# CajitaAbierta_v07_robotique.net
KiCad netlist of a schematic drawn in EAGLE
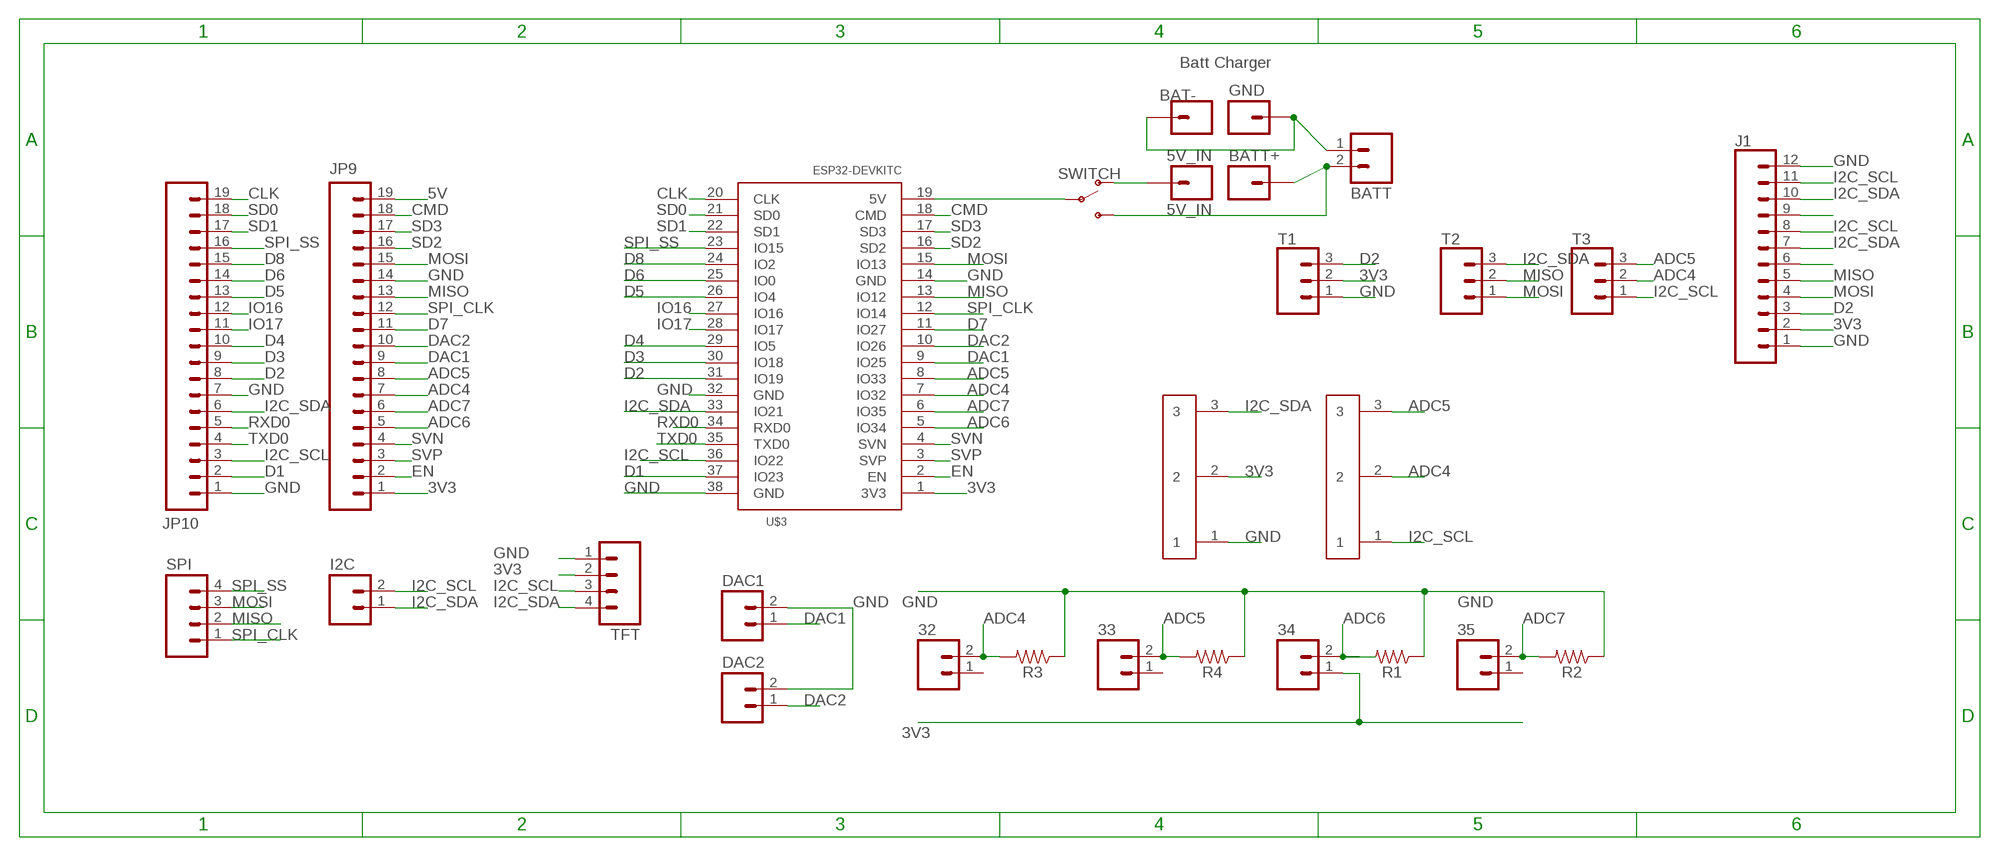
[diagram p0: schematic, sheet 1]

(export (version "E")
  (design (tool "Eeschema 10.0.6"))
  (components
    (comp (ref "5V_IN")
      (value "5V_IN")
      (footprint "eagle-import:1X01")
      (libsource (lib "eagle-import") (part "M01PTH"))
    )
    (comp (ref "32")
      (value "M02PTH")
      (footprint "eagle-import:1X02")
      (libsource (lib "eagle-import") (part "SparkFun-Connectors_6242394_M02PTH"))
    )
    (comp (ref "33")
      (value "M02PTH")
      (footprint "eagle-import:1X02")
      (libsource (lib "eagle-import") (part "SparkFun-Connectors_6242394_M02PTH"))
    )
    (comp (ref "34")
      (value "M02PTH")
      (footprint "eagle-import:1X02")
      (libsource (lib "eagle-import") (part "SparkFun-Connectors_6242394_M02PTH"))
    )
    (comp (ref "35")
      (value "M02PTH")
      (footprint "eagle-import:1X02")
      (libsource (lib "eagle-import") (part "SparkFun-Connectors_6242394_M02PTH"))
    )
    (comp (ref "BAT-")
      (value "M01PTH")
      (footprint "eagle-import:1X01")
      (libsource (lib "eagle-import") (part "M01PTH"))
    )
    (comp (ref "BATT")
      (value "M02LOCK_LONGPADS")
      (footprint "eagle-import:1X02_LOCK_LONGPADS")
      (libsource (lib "eagle-import") (part "M02LOCK_LONGPADS"))
    )
    (comp (ref "BATT+")
      (value "M01PTH")
      (footprint "eagle-import:1X01")
      (libsource (lib "eagle-import") (part "M01PTH"))
    )
    (comp (ref "DAC1")
      (value "M02PTH")
      (footprint "eagle-import:1X02")
      (libsource (lib "eagle-import") (part "SparkFun-Connectors_6242394_M02PTH"))
    )
    (comp (ref "DAC2")
      (value "M02PTH")
      (footprint "eagle-import:1X02")
      (libsource (lib "eagle-import") (part "SparkFun-Connectors_6242394_M02PTH"))
    )
    (comp (ref "GND")
      (value "Batt Charger")
      (footprint "eagle-import:1X01")
      (libsource (lib "eagle-import") (part "M01PTH"))
    )
    (comp (ref "I2C")
      (value "M02PTH")
      (footprint "eagle-import:1X02")
      (libsource (lib "eagle-import") (part "SparkFun-Connectors_6242394_M02PTH"))
    )
    (comp (ref "J1")
      (value "CONN_12NO_SILK")
      (footprint "eagle-import:1X12_NO_SILK")
      (libsource (lib "eagle-import") (part "CONN_12NO_SILK"))
    )
    (comp (ref "JP9")
      (value "M191X19")
      (footprint "eagle-import:1X19")
      (libsource (lib "eagle-import") (part "M191X19"))
    )
    (comp (ref "JP10")
      (value "M191X19")
      (footprint "eagle-import:1X19")
      (libsource (lib "eagle-import") (part "M191X19"))
    )
    (comp (ref "R1")
      (value "RESISTOR1206")
      (footprint "eagle-import:1206")
      (libsource (lib "eagle-import") (part "RESISTOR1206"))
    )
    (comp (ref "R2")
      (value "RESISTOR1206")
      (footprint "eagle-import:1206")
      (libsource (lib "eagle-import") (part "RESISTOR1206"))
    )
    (comp (ref "R3")
      (value "RESISTOR1206")
      (footprint "eagle-import:1206")
      (libsource (lib "eagle-import") (part "RESISTOR1206"))
    )
    (comp (ref "R4")
      (value "RESISTOR1206")
      (footprint "eagle-import:1206")
      (libsource (lib "eagle-import") (part "RESISTOR1206"))
    )
    (comp (ref "SPI")
      (value "M04PTH")
      (footprint "eagle-import:1X04")
      (libsource (lib "eagle-import") (part "M04PTH"))
    )
    (comp (ref "SWITCH")
      (value "SWITCH-SPDT-SMD-RIGHT-ANGLE")
      (footprint "eagle-import:SWITCH_SPST_SMD_A")
      (libsource (lib "eagle-import") (part "SWITCH-SPDT-SMD-RIGHT-ANGLE"))
    )
    (comp (ref "T1")
      (value "CONN_03SCREW-NS")
      (footprint "eagle-import:SCREWTERMINAL-3.5MM-3-NS")
      (libsource (lib "eagle-import") (part "CONN_03SCREW-NS"))
    )
    (comp (ref "T2")
      (value "CONN_03SCREW-NS")
      (footprint "eagle-import:SCREWTERMINAL-3.5MM-3-NS")
      (libsource (lib "eagle-import") (part "CONN_03SCREW-NS"))
    )
    (comp (ref "T3")
      (value "CONN_03SCREW-NS")
      (footprint "eagle-import:SCREWTERMINAL-3.5MM-3-NS")
      (libsource (lib "eagle-import") (part "CONN_03SCREW-NS"))
    )
    (comp (ref "TFT")
      (value "M04PTH")
      (footprint "eagle-import:1X04")
      (libsource (lib "eagle-import") (part "M04PTH"))
    )
    (comp (ref "U$3")
      (value "ESP32DEVKITC")
      (footprint "eagle-import:ESP32-DEVKITC")
      (libsource (lib "eagle-import") (part "ESP32DEVKITC"))
    )
    (comp (ref "U$4")
      (value "SCREW_TERMINAL_3_POS_5MM")
      (footprint "eagle-import:SCREW_TERMINAL_3_POS_5MM")
      (libsource (lib "eagle-import") (part "SCREW_TERMINAL_3_POS_5MM"))
    )
    (comp (ref "U$5")
      (value "SCREW_TERMINAL_3_POS_5MM")
      (footprint "eagle-import:SCREW_TERMINAL_3_POS_5MM")
      (libsource (lib "eagle-import") (part "SCREW_TERMINAL_3_POS_5MM"))
    )
  )
  (nets
    (net (code "1") (name "/3V3") (class "Default")
      (node (ref "34") (pin "1") (pinfunction "1_1") (pintype "passive"))
      (node (ref "J1") (pin "2") (pinfunction "2_2") (pintype "passive"))
      (node (ref "JP9") (pin "1") (pinfunction "1_1") (pintype "passive"))
      (node (ref "T1") (pin "2") (pinfunction "2_2") (pintype "passive"))
      (node (ref "TFT") (pin "2") (pinfunction "2_2") (pintype "passive"))
      (node (ref "U$3") (pin "1") (pinfunction "3V3_1") (pintype "bidirectional"))
      (node (ref "U$4") (pin "2") (pinfunction "2_2") (pintype "bidirectional"))
    )
    (net (code "2") (name "/5V") (class "Default")
      (node (ref "JP9") (pin "19") (pinfunction "19_19") (pintype "passive"))
      (node (ref "SWITCH") (pin "2") (pinfunction "P_2") (pintype "passive"))
      (node (ref "U$3") (pin "19") (pinfunction "5V_19") (pintype "bidirectional"))
    )
    (net (code "3") (name "/ADC4") (class "Default")
      (node (ref "32") (pin "2") (pinfunction "2_2") (pintype "passive"))
      (node (ref "JP9") (pin "7") (pinfunction "7_7") (pintype "passive"))
      (node (ref "R3") (pin "2") (pinfunction "2_2") (pintype "passive"))
      (node (ref "T3") (pin "2") (pinfunction "2_2") (pintype "passive"))
      (node (ref "U$3") (pin "7") (pinfunction "IO32_7") (pintype "bidirectional"))
      (node (ref "U$5") (pin "2") (pinfunction "2_2") (pintype "bidirectional"))
    )
    (net (code "4") (name "/ADC5") (class "Default")
      (node (ref "33") (pin "2") (pinfunction "2_2") (pintype "passive"))
      (node (ref "JP9") (pin "8") (pinfunction "8_8") (pintype "passive"))
      (node (ref "R4") (pin "2") (pinfunction "2_2") (pintype "passive"))
      (node (ref "T3") (pin "3") (pinfunction "3_3") (pintype "passive"))
      (node (ref "U$3") (pin "8") (pinfunction "IO33_8") (pintype "bidirectional"))
      (node (ref "U$5") (pin "3") (pinfunction "3_3") (pintype "bidirectional"))
    )
    (net (code "5") (name "/ADC6") (class "Default")
      (node (ref "34") (pin "2") (pinfunction "2_2") (pintype "passive"))
      (node (ref "JP9") (pin "5") (pinfunction "5_5") (pintype "passive"))
      (node (ref "R1") (pin "2") (pinfunction "2_2") (pintype "passive"))
      (node (ref "U$3") (pin "5") (pinfunction "IO34_5") (pintype "bidirectional"))
    )
    (net (code "6") (name "/ADC7") (class "Default")
      (node (ref "35") (pin "2") (pinfunction "2_2") (pintype "passive"))
      (node (ref "JP9") (pin "6") (pinfunction "6_6") (pintype "passive"))
      (node (ref "R2") (pin "2") (pinfunction "2_2") (pintype "passive"))
      (node (ref "U$3") (pin "6") (pinfunction "IO35_6") (pintype "bidirectional"))
    )
    (net (code "7") (name "/CLK") (class "Default")
      (node (ref "JP10") (pin "19") (pinfunction "19_19") (pintype "passive"))
      (node (ref "U$3") (pin "20") (pinfunction "CLK_20") (pintype "bidirectional"))
    )
    (net (code "8") (name "/CMD") (class "Default")
      (node (ref "JP9") (pin "18") (pinfunction "18_18") (pintype "passive"))
      (node (ref "U$3") (pin "18") (pinfunction "CMD_18") (pintype "bidirectional"))
    )
    (net (code "9") (name "/D1") (class "Default")
      (node (ref "JP10") (pin "2") (pinfunction "2_2") (pintype "passive"))
      (node (ref "U$3") (pin "37") (pinfunction "IO23_37") (pintype "bidirectional"))
    )
    (net (code "10") (name "/D2") (class "Default")
      (node (ref "J1") (pin "3") (pinfunction "3_3") (pintype "passive"))
      (node (ref "JP10") (pin "8") (pinfunction "8_8") (pintype "passive"))
      (node (ref "T1") (pin "3") (pinfunction "3_3") (pintype "passive"))
      (node (ref "U$3") (pin "31") (pinfunction "IO19_31") (pintype "bidirectional"))
    )
    (net (code "11") (name "/D3") (class "Default")
      (node (ref "JP10") (pin "9") (pinfunction "9_9") (pintype "passive"))
      (node (ref "U$3") (pin "30") (pinfunction "IO18_30") (pintype "bidirectional"))
    )
    (net (code "12") (name "/D4") (class "Default")
      (node (ref "JP10") (pin "10") (pinfunction "10_10") (pintype "passive"))
      (node (ref "U$3") (pin "29") (pinfunction "IO5_29") (pintype "bidirectional"))
    )
    (net (code "13") (name "/D5") (class "Default")
      (node (ref "JP10") (pin "13") (pinfunction "13_13") (pintype "passive"))
      (node (ref "U$3") (pin "26") (pinfunction "IO4_26") (pintype "bidirectional"))
    )
    (net (code "14") (name "/D6") (class "Default")
      (node (ref "JP10") (pin "14") (pinfunction "14_14") (pintype "passive"))
      (node (ref "U$3") (pin "25") (pinfunction "IO0_25") (pintype "bidirectional"))
    )
    (net (code "15") (name "/D7") (class "Default")
      (node (ref "JP9") (pin "11") (pinfunction "11_11") (pintype "passive"))
      (node (ref "U$3") (pin "11") (pinfunction "IO27_11") (pintype "bidirectional"))
    )
    (net (code "16") (name "/D8") (class "Default")
      (node (ref "JP10") (pin "15") (pinfunction "15_15") (pintype "passive"))
      (node (ref "U$3") (pin "24") (pinfunction "IO2_24") (pintype "bidirectional"))
    )
    (net (code "17") (name "/DAC1") (class "Default")
      (node (ref "DAC1") (pin "1") (pinfunction "1_1") (pintype "passive"))
      (node (ref "JP9") (pin "9") (pinfunction "9_9") (pintype "passive"))
      (node (ref "U$3") (pin "9") (pinfunction "IO25_9") (pintype "bidirectional"))
    )
    (net (code "18") (name "/DAC2") (class "Default")
      (node (ref "DAC2") (pin "1") (pinfunction "1_1") (pintype "passive"))
      (node (ref "JP9") (pin "10") (pinfunction "10_10") (pintype "passive"))
      (node (ref "U$3") (pin "10") (pinfunction "IO26_10") (pintype "bidirectional"))
    )
    (net (code "19") (name "/EN") (class "Default")
      (node (ref "JP9") (pin "2") (pinfunction "2_2") (pintype "passive"))
      (node (ref "U$3") (pin "2") (pinfunction "EN_2") (pintype "bidirectional"))
    )
    (net (code "20") (name "/GND") (class "Default")
      (node (ref "BAT-") (pin "1") (pinfunction "1_1") (pintype "passive"))
      (node (ref "BATT") (pin "1") (pinfunction "1_1") (pintype "passive"))
      (node (ref "DAC1") (pin "2") (pinfunction "2_2") (pintype "passive"))
      (node (ref "DAC2") (pin "2") (pinfunction "2_2") (pintype "passive"))
      (node (ref "GND") (pin "1") (pinfunction "1_1") (pintype "passive"))
      (node (ref "J1") (pin "1") (pinfunction "1_1") (pintype "passive"))
      (node (ref "J1") (pin "12") (pinfunction "12_12") (pintype "passive"))
      (node (ref "JP10") (pin "1") (pinfunction "1_1") (pintype "passive"))
      (node (ref "JP10") (pin "7") (pinfunction "7_7") (pintype "passive"))
      (node (ref "JP9") (pin "14") (pinfunction "14_14") (pintype "passive"))
      (node (ref "R1") (pin "1") (pinfunction "1_1") (pintype "passive"))
      (node (ref "R2") (pin "1") (pinfunction "1_1") (pintype "passive"))
      (node (ref "R3") (pin "1") (pinfunction "1_1") (pintype "passive"))
      (node (ref "R4") (pin "1") (pinfunction "1_1") (pintype "passive"))
      (node (ref "T1") (pin "1") (pinfunction "1_1") (pintype "passive"))
      (node (ref "TFT") (pin "1") (pinfunction "1_1") (pintype "passive"))
      (node (ref "U$3") (pin "14") (pinfunction "GND_14") (pintype "bidirectional"))
      (node (ref "U$3") (pin "32") (pinfunction "GND_32") (pintype "bidirectional"))
      (node (ref "U$3") (pin "38") (pinfunction "GND_38") (pintype "bidirectional"))
      (node (ref "U$4") (pin "1") (pinfunction "1_1") (pintype "bidirectional"))
    )
    (net (code "21") (name "/I2C_SCL") (class "Default")
      (node (ref "I2C") (pin "2") (pinfunction "2_2") (pintype "passive"))
      (node (ref "J1") (pin "11") (pinfunction "11_11") (pintype "passive"))
      (node (ref "J1") (pin "8") (pinfunction "8_8") (pintype "passive"))
      (node (ref "JP10") (pin "3") (pinfunction "3_3") (pintype "passive"))
      (node (ref "T3") (pin "1") (pinfunction "1_1") (pintype "passive"))
      (node (ref "TFT") (pin "3") (pinfunction "3_3") (pintype "passive"))
      (node (ref "U$3") (pin "36") (pinfunction "IO22_36") (pintype "bidirectional"))
      (node (ref "U$5") (pin "1") (pinfunction "1_1") (pintype "bidirectional"))
    )
    (net (code "22") (name "/I2C_SDA") (class "Default")
      (node (ref "I2C") (pin "1") (pinfunction "1_1") (pintype "passive"))
      (node (ref "J1") (pin "10") (pinfunction "10_10") (pintype "passive"))
      (node (ref "J1") (pin "7") (pinfunction "7_7") (pintype "passive"))
      (node (ref "JP10") (pin "6") (pinfunction "6_6") (pintype "passive"))
      (node (ref "T2") (pin "3") (pinfunction "3_3") (pintype "passive"))
      (node (ref "TFT") (pin "4") (pinfunction "4_4") (pintype "passive"))
      (node (ref "U$3") (pin "33") (pinfunction "IO21_33") (pintype "bidirectional"))
      (node (ref "U$4") (pin "3") (pinfunction "3_3") (pintype "bidirectional"))
    )
    (net (code "23") (name "/IO16") (class "Default")
      (node (ref "JP10") (pin "12") (pinfunction "12_12") (pintype "passive"))
      (node (ref "U$3") (pin "27") (pinfunction "IO16_27") (pintype "bidirectional"))
    )
    (net (code "24") (name "/IO17") (class "Default")
      (node (ref "JP10") (pin "11") (pinfunction "11_11") (pintype "passive"))
      (node (ref "U$3") (pin "28") (pinfunction "IO17_28") (pintype "bidirectional"))
    )
    (net (code "25") (name "/MISO") (class "Default")
      (node (ref "J1") (pin "5") (pinfunction "5_5") (pintype "passive"))
      (node (ref "JP9") (pin "13") (pinfunction "13_13") (pintype "passive"))
      (node (ref "SPI") (pin "2") (pinfunction "2_2") (pintype "passive"))
      (node (ref "T2") (pin "2") (pinfunction "2_2") (pintype "passive"))
      (node (ref "U$3") (pin "13") (pinfunction "IO12_13") (pintype "bidirectional"))
    )
    (net (code "26") (name "/MOSI") (class "Default")
      (node (ref "J1") (pin "4") (pinfunction "4_4") (pintype "passive"))
      (node (ref "JP9") (pin "15") (pinfunction "15_15") (pintype "passive"))
      (node (ref "SPI") (pin "3") (pinfunction "3_3") (pintype "passive"))
      (node (ref "T2") (pin "1") (pinfunction "1_1") (pintype "passive"))
      (node (ref "U$3") (pin "15") (pinfunction "IO13_15") (pintype "bidirectional"))
    )
    (net (code "27") (name "/RXD0") (class "Default")
      (node (ref "JP10") (pin "5") (pinfunction "5_5") (pintype "passive"))
      (node (ref "U$3") (pin "34") (pinfunction "RXD0_34") (pintype "bidirectional"))
    )
    (net (code "28") (name "/SD0") (class "Default")
      (node (ref "JP10") (pin "18") (pinfunction "18_18") (pintype "passive"))
      (node (ref "U$3") (pin "21") (pinfunction "SD0_21") (pintype "bidirectional"))
    )
    (net (code "29") (name "/SD1") (class "Default")
      (node (ref "JP10") (pin "17") (pinfunction "17_17") (pintype "passive"))
      (node (ref "U$3") (pin "22") (pinfunction "SD1_22") (pintype "bidirectional"))
    )
    (net (code "30") (name "/SD2") (class "Default")
      (node (ref "JP9") (pin "16") (pinfunction "16_16") (pintype "passive"))
      (node (ref "U$3") (pin "16") (pinfunction "SD2_16") (pintype "bidirectional"))
    )
    (net (code "31") (name "/SD3") (class "Default")
      (node (ref "JP9") (pin "17") (pinfunction "17_17") (pintype "passive"))
      (node (ref "U$3") (pin "17") (pinfunction "SD3_17") (pintype "bidirectional"))
    )
    (net (code "32") (name "/SPI_CLK") (class "Default")
      (node (ref "JP9") (pin "12") (pinfunction "12_12") (pintype "passive"))
      (node (ref "SPI") (pin "1") (pinfunction "1_1") (pintype "passive"))
      (node (ref "U$3") (pin "12") (pinfunction "IO14_12") (pintype "bidirectional"))
    )
    (net (code "33") (name "/SPI_SS") (class "Default")
      (node (ref "JP10") (pin "16") (pinfunction "16_16") (pintype "passive"))
      (node (ref "SPI") (pin "4") (pinfunction "4_4") (pintype "passive"))
      (node (ref "U$3") (pin "23") (pinfunction "IO15_23") (pintype "bidirectional"))
    )
    (net (code "34") (name "/SVN") (class "Default")
      (node (ref "JP9") (pin "4") (pinfunction "4_4") (pintype "passive"))
      (node (ref "U$3") (pin "4") (pinfunction "SVN_4") (pintype "bidirectional"))
    )
    (net (code "35") (name "/SVP") (class "Default")
      (node (ref "JP9") (pin "3") (pinfunction "3_3") (pintype "passive"))
      (node (ref "U$3") (pin "3") (pinfunction "SVP_3") (pintype "bidirectional"))
    )
    (net (code "36") (name "/TXD0") (class "Default")
      (node (ref "JP10") (pin "4") (pinfunction "4_4") (pintype "passive"))
      (node (ref "U$3") (pin "35") (pinfunction "TXD0_35") (pintype "bidirectional"))
    )
    (net (code "37") (name "Net-(SWITCH-O)") (class "Default")
      (node (ref "5V_IN") (pin "1") (pinfunction "1_1") (pintype "passive"))
      (node (ref "SWITCH") (pin "1") (pinfunction "O_1") (pintype "passive"))
    )
    (net (code "38") (name "Net-(SWITCH-S)") (class "Default")
      (node (ref "BATT") (pin "2") (pinfunction "2_2") (pintype "passive"))
      (node (ref "BATT+") (pin "1") (pinfunction "1_1") (pintype "passive"))
      (node (ref "SWITCH") (pin "3") (pinfunction "S_3") (pintype "passive"))
    )
    (net (code "39") (name "unconnected-(32-Pad1)") (class "Default")
      (node (ref "32") (pin "1") (pinfunction "1_1") (pintype "passive"))
    )
    (net (code "40") (name "unconnected-(33-Pad1)") (class "Default")
      (node (ref "33") (pin "1") (pinfunction "1_1") (pintype "passive"))
    )
    (net (code "41") (name "unconnected-(35-Pad1)") (class "Default")
      (node (ref "35") (pin "1") (pinfunction "1_1") (pintype "passive"))
    )
    (net (code "42") (name "unconnected-(J1-Pad6)") (class "Default")
      (node (ref "J1") (pin "6") (pinfunction "6_6") (pintype "passive"))
    )
    (net (code "43") (name "unconnected-(J1-Pad9)") (class "Default")
      (node (ref "J1") (pin "9") (pinfunction "9_9") (pintype "passive"))
    )
  )
)
